# MCU.net
KiCad netlist of a schematic drawn in Altium Designer
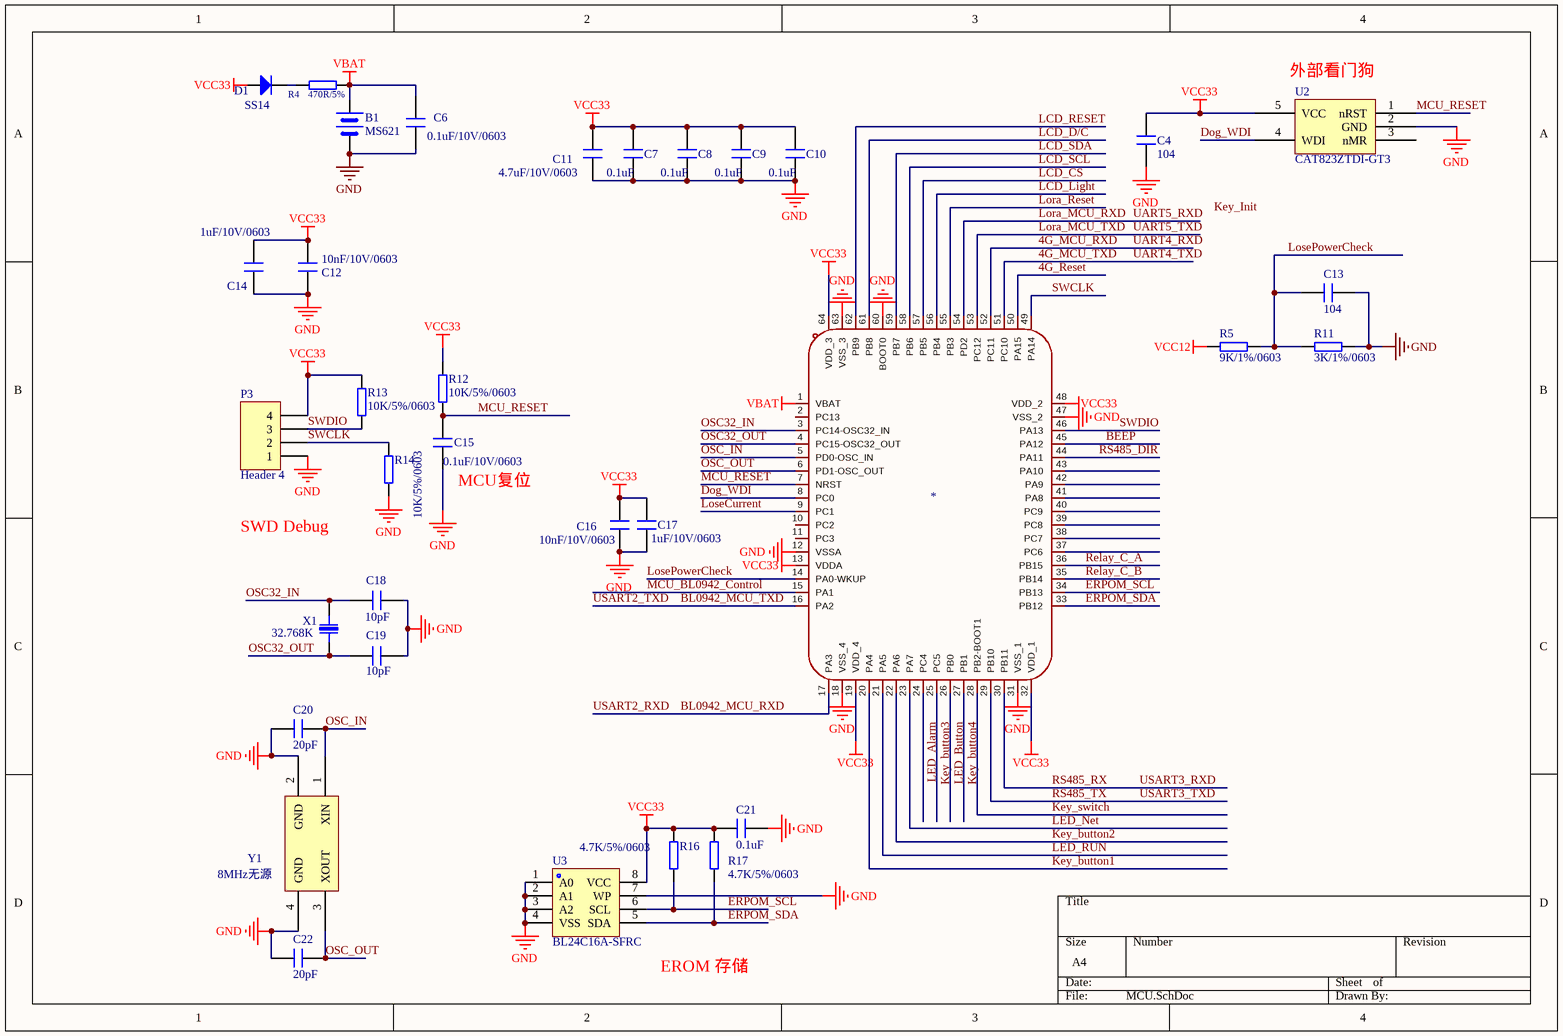
[diagram p0: MCU.SchDoc]

(export (version "E")
  (design (tool "Eeschema 10.0.6"))
  (components
    (comp (ref "B1") (value "MS621") (footprint "MS621") (libsource (lib "ES_Schematic") (part "BATTERY")))
    (comp (ref "C4") (value "104") (footprint "0603R") (libsource (lib "ES_Schematic") (part "CAP")))
    (comp (ref "C6")
      (value "0.1uF/10V/0603")
      (footprint "0603R")
      (libsource (lib "ES_Schematic") (part "CAP_1"))
    )
    (comp (ref "C7") (value "0.1uF") (footprint "0603R") (libsource (lib "ES_Schematic") (part "CAP_1")))
    (comp (ref "C8") (value "0.1uF") (footprint "0603R") (libsource (lib "ES_Schematic") (part "CAP_1")))
    (comp (ref "C9") (value "0.1uF") (footprint "0603R") (libsource (lib "ES_Schematic") (part "CAP_1")))
    (comp (ref "C10") (value "0.1uF") (footprint "0603R") (libsource (lib "ES_Schematic") (part "CAP_1")))
    (comp (ref "C11")
      (value "4.7uF/10V/0603")
      (footprint "0603R")
      (libsource (lib "ES_Schematic") (part "CAP_1"))
    )
    (comp (ref "C12")
      (value "10nF/10V/0603")
      (footprint "0603R")
      (libsource (lib "ES_Schematic") (part "CAP_1"))
    )
    (comp (ref "C13") (value "104") (footprint "0603R") (libsource (lib "ES_Schematic") (part "CAP")))
    (comp (ref "C14")
      (value "1uF/10V/0603")
      (footprint "0603R")
      (libsource (lib "ES_Schematic") (part "CAP_1"))
    )
    (comp (ref "C15")
      (value "0.1uF/10V/0603")
      (footprint "0603R")
      (libsource (lib "ES_Schematic") (part "CAP_1"))
    )
    (comp (ref "C16")
      (value "10nF/10V/0603")
      (footprint "0603R")
      (libsource (lib "ES_Schematic") (part "CAP_1"))
    )
    (comp (ref "C17")
      (value "1uF/10V/0603")
      (footprint "0603R")
      (libsource (lib "ES_Schematic") (part "CAP_1"))
    )
    (comp (ref "C18") (value "10pF") (footprint "0603r") (libsource (lib "ES_Schematic") (part "CAP")))
    (comp (ref "C19") (value "10pF") (footprint "0603r") (libsource (lib "ES_Schematic") (part "CAP")))
    (comp (ref "C20") (value "20pF") (footprint "0603r") (libsource (lib "ES_Schematic") (part "CAP")))
    (comp (ref "C21") (value "0.1uF") (footprint "0603R") (libsource (lib "ES_Schematic") (part "CAP_1")))
    (comp (ref "C22") (value "20pF") (footprint "0603r") (libsource (lib "ES_Schematic") (part "CAP")))
    (comp (ref "D1") (value "SS14") (footprint "SOD323") (libsource (lib "ES_Schematic") (part "DIODE")))
    (comp (ref "P3")
      (value "Header 4")
      (footprint "HDR1X4")
      (description "Header, 4-Pin")
      (fields (field (name "PUBLISHER") "Altium Limited"))
      (libsource (lib "Miscellaneous Connectors") (part "Header 4"))
    )
    (comp (ref "R4") (value "470R/5%") (footprint "0603R") (libsource (lib "ES_Schematic") (part "RES")))
    (comp (ref "R5") (value "9K/1%/0603") (footprint "0603R") (libsource (lib "ES_Schematic") (part "RES")))
    (comp (ref "R11") (value "3K/1%/0603") (footprint "0603R") (libsource (lib "ES_Schematic") (part "RES")))
    (comp (ref "R12") (value "10K/5%/0603") (footprint "0603r") (libsource (lib "ES_Schematic") (part "RES")))
    (comp (ref "R13") (value "10K/5%/0603") (footprint "0603r") (libsource (lib "ES_Schematic") (part "RES")))
    (comp (ref "R14") (value "10K/5%/0603") (footprint "0603r") (libsource (lib "ES_Schematic") (part "RES")))
    (comp (ref "R16")
      (value "4.7K/5%/0603")
      (footprint "0603R")
      (libsource (lib "ES_Schematic") (part "RES"))
    )
    (comp (ref "R17")
      (value "4.7K/5%/0603")
      (footprint "0603R")
      (libsource (lib "ES_Schematic") (part "RES"))
    )
    (comp (ref "U1")
      (value "*")
      (footprint "LQFP64")
      (libsource (lib "altium-import") (part "root_0_N32G452REL7_"))
    )
    (comp (ref "U2")
      (value "CAT823ZTDI-GT3")
      (footprint "SOT-23-5")
      (libsource (lib "ES_Schematic") (part "CAT823"))
    )
    (comp (ref "U3")
      (value "BL24C16A-SFRC")
      (footprint "TSSOP8")
      (libsource (lib "ES_Schematic") (part "24LC02"))
    )
    (comp (ref "X1") (value "32.768K") (footprint "Y3215") (libsource (lib "ES_Schematic") (part "XTAL")))
    (comp (ref "Y1") (value "8MHz无源") (footprint "3225") (libsource (lib "others") (part "12MHz无源")))
  )
  (nets
    (net (code "1") (name "/4G_MCU_RXD") (class "Default")
      (node (ref "U1") (pin "52") (pinfunction "PC11_52") (pintype "passive"))
    )
    (net (code "2") (name "/4G_MCU_TXD") (class "Default")
      (node (ref "U1") (pin "51") (pinfunction "PC10_51") (pintype "passive"))
    )
    (net (code "3") (name "/4G_Reset") (class "Default")
      (node (ref "U1") (pin "50") (pinfunction "PA15_50") (pintype "passive"))
    )
    (net (code "4") (name "/BEEP") (class "Default")
      (node (ref "U1") (pin "45") (pinfunction "PA12_45") (pintype "passive"))
    )
    (net (code "5") (name "/BL0942_MCU_RXD") (class "Default")
      (node (ref "U1") (pin "17") (pinfunction "PA3_17") (pintype "passive"))
    )
    (net (code "6") (name "/BL0942_MCU_TXD") (class "Default")
      (node (ref "U1") (pin "16") (pinfunction "PA2_16") (pintype "passive"))
    )
    (net (code "7") (name "/Dog_WDI") (class "Default")
      (node (ref "U1") (pin "8") (pinfunction "PC0_8") (pintype "passive"))
      (node (ref "U2") (pin "4") (pinfunction "WDI_4") (pintype "passive"))
    )
    (net (code "8") (name "/ERPOM_SCL") (class "Default")
      (node (ref "R16") (pin "2") (pinfunction "2_2") (pintype "passive"))
      (node (ref "U1") (pin "34") (pinfunction "PB13_34") (pintype "passive"))
      (node (ref "U3") (pin "6") (pinfunction "SCL_6") (pintype "passive"))
    )
    (net (code "9") (name "/ERPOM_SDA") (class "Default")
      (node (ref "R17") (pin "2") (pinfunction "2_2") (pintype "passive"))
      (node (ref "U1") (pin "33") (pinfunction "PB12_33") (pintype "passive"))
      (node (ref "U3") (pin "5") (pinfunction "SDA_5") (pintype "passive"))
    )
    (net (code "11") (name "/Key_button1") (class "Default")
      (node (ref "U1") (pin "20") (pinfunction "PA4_20") (pintype "passive"))
    )
    (net (code "12") (name "/Key_button2") (class "Default")
      (node (ref "U1") (pin "22") (pinfunction "PA6_22") (pintype "passive"))
    )
    (net (code "13") (name "/Key_button3") (class "Default")
      (node (ref "U1") (pin "25") (pinfunction "PC5_25") (pintype "passive"))
    )
    (net (code "14") (name "/Key_button4") (class "Default")
      (node (ref "U1") (pin "27") (pinfunction "PB1_27") (pintype "passive"))
    )
    (net (code "15") (name "/Key_switch") (class "Default")
      (node (ref "U1") (pin "28") (pinfunction "PB2-BOOT1_28") (pintype "passive"))
    )
    (net (code "16") (name "/LCD_CS") (class "Default")
      (node (ref "U1") (pin "57") (pinfunction "PB5_57") (pintype "passive"))
    )
    (net (code "17") (name "/LCD_D{slash}C") (class "Default")
      (node (ref "U1") (pin "61") (pinfunction "PB8_61") (pintype "passive"))
    )
    (net (code "18") (name "/LCD_Light") (class "Default")
      (node (ref "U1") (pin "56") (pinfunction "PB4_56") (pintype "passive"))
    )
    (net (code "19") (name "/LCD_RESET") (class "Default")
      (node (ref "U1") (pin "62") (pinfunction "PB9_62") (pintype "passive"))
    )
    (net (code "20") (name "/LCD_SCL") (class "Default")
      (node (ref "U1") (pin "58") (pinfunction "PB6_58") (pintype "passive"))
    )
    (net (code "21") (name "/LCD_SDA") (class "Default")
      (node (ref "U1") (pin "59") (pinfunction "PB7_59") (pintype "passive"))
    )
    (net (code "22") (name "/LED_Alarm") (class "Default")
      (node (ref "U1") (pin "24") (pinfunction "PC4_24") (pintype "passive"))
    )
    (net (code "23") (name "/LED_Button") (class "Default")
      (node (ref "U1") (pin "26") (pinfunction "PB0_26") (pintype "passive"))
    )
    (net (code "24") (name "/LED_Net") (class "Default")
      (node (ref "U1") (pin "23") (pinfunction "PA7_23") (pintype "passive"))
    )
    (net (code "25") (name "/LED_RUN") (class "Default")
      (node (ref "U1") (pin "21") (pinfunction "PA5_21") (pintype "passive"))
    )
    (net (code "26") (name "/Lora_MCU_RXD") (class "Default")
      (node (ref "U1") (pin "54") (pinfunction "PD2_54") (pintype "passive"))
    )
    (net (code "27") (name "/Lora_MCU_TXD") (class "Default")
      (node (ref "U1") (pin "53") (pinfunction "PC12_53") (pintype "passive"))
    )
    (net (code "28") (name "/Lora_Reset") (class "Default")
      (node (ref "U1") (pin "55") (pinfunction "PB3_55") (pintype "passive"))
    )
    (net (code "29") (name "/LoseCurrent") (class "Default")
      (node (ref "U1") (pin "9") (pinfunction "PC1_9") (pintype "passive"))
    )
    (net (code "30") (name "/LosePowerCheck") (class "Default")
      (node (ref "C13") (pin "2") (pinfunction "2_2") (pintype "passive"))
      (node (ref "R11") (pin "2") (pinfunction "2_2") (pintype "passive"))
      (node (ref "R5") (pin "2") (pinfunction "2_2") (pintype "passive"))
      (node (ref "U1") (pin "14") (pinfunction "PA0-WKUP_14") (pintype "passive"))
    )
    (net (code "31") (name "/MCU_BL0942_Control") (class "Default")
      (node (ref "U1") (pin "15") (pinfunction "PA1_15") (pintype "passive"))
    )
    (net (code "32") (name "/MCU_RESET") (class "Default")
      (node (ref "C15") (pin "2") (pinfunction "2_2") (pintype "passive"))
      (node (ref "R12") (pin "1") (pinfunction "1_1") (pintype "passive"))
      (node (ref "U1") (pin "7") (pinfunction "NRST_7") (pintype "passive"))
      (node (ref "U2") (pin "1") (pinfunction "nRST_1") (pintype "passive"))
    )
    (net (code "33") (name "/OSC32_IN") (class "Default")
      (node (ref "C18") (pin "1") (pinfunction "1_1") (pintype "passive"))
      (node (ref "U1") (pin "3") (pinfunction "PC14-OSC32_IN_3") (pintype "passive"))
      (node (ref "X1") (pin "2") (pinfunction "2_2") (pintype "passive"))
    )
    (net (code "34") (name "/OSC32_OUT") (class "Default")
      (node (ref "C19") (pin "2") (pinfunction "2_2") (pintype "passive"))
      (node (ref "U1") (pin "4") (pinfunction "PC15-OSC32_OUT_4") (pintype "passive"))
      (node (ref "X1") (pin "1") (pinfunction "1_1") (pintype "passive"))
    )
    (net (code "35") (name "/OSC_IN") (class "Default")
      (node (ref "C20") (pin "2") (pinfunction "2_2") (pintype "passive"))
      (node (ref "U1") (pin "5") (pinfunction "PD0-OSC_IN_5") (pintype "passive"))
      (node (ref "Y1") (pin "1") (pinfunction "XIN_1") (pintype "passive"))
    )
    (net (code "36") (name "/OSC_OUT") (class "Default")
      (node (ref "C22") (pin "2") (pinfunction "2_2") (pintype "passive"))
      (node (ref "U1") (pin "6") (pinfunction "PD1-OSC_OUT_6") (pintype "passive"))
      (node (ref "Y1") (pin "3") (pinfunction "XOUT_3") (pintype "passive"))
    )
    (net (code "37") (name "/RS485_DIR") (class "Default")
      (node (ref "U1") (pin "44") (pinfunction "PA11_44") (pintype "passive"))
    )
    (net (code "38") (name "/RS485_RX") (class "Default")
      (node (ref "U1") (pin "30") (pinfunction "PB11_30") (pintype "passive"))
    )
    (net (code "39") (name "/RS485_TX") (class "Default")
      (node (ref "U1") (pin "29") (pinfunction "PB10_29") (pintype "passive"))
    )
    (net (code "40") (name "/Relay_C_A") (class "Default")
      (node (ref "U1") (pin "36") (pinfunction "PB15_36") (pintype "passive"))
    )
    (net (code "41") (name "/Relay_C_B") (class "Default")
      (node (ref "U1") (pin "35") (pinfunction "PB14_35") (pintype "passive"))
    )
    (net (code "42") (name "/SWCLK") (class "Default")
      (node (ref "P3") (pin "2") (pinfunction "2_2") (pintype "passive"))
      (node (ref "R14") (pin "2") (pinfunction "2_2") (pintype "passive"))
      (node (ref "U1") (pin "49") (pinfunction "PA14_49") (pintype "passive"))
    )
    (net (code "43") (name "/SWDIO") (class "Default")
      (node (ref "P3") (pin "3") (pinfunction "3_3") (pintype "passive"))
      (node (ref "R13") (pin "1") (pinfunction "1_1") (pintype "passive"))
      (node (ref "U1") (pin "46") (pinfunction "PA13_46") (pintype "passive"))
    )
    (net (code "44") (name "GND") (class "Default")
      (node (ref "B1") (pin "2") (pinfunction "2_2") (pintype "passive"))
      (node (ref "C10") (pin "1") (pinfunction "1_1") (pintype "passive"))
      (node (ref "C11") (pin "1") (pinfunction "1_1") (pintype "passive"))
      (node (ref "C12") (pin "1") (pinfunction "1_1") (pintype "passive"))
      (node (ref "C13") (pin "1") (pinfunction "1_1") (pintype "passive"))
      (node (ref "C14") (pin "1") (pinfunction "1_1") (pintype "passive"))
      (node (ref "C15") (pin "1") (pinfunction "1_1") (pintype "passive"))
      (node (ref "C16") (pin "1") (pinfunction "1_1") (pintype "passive"))
      (node (ref "C17") (pin "1") (pinfunction "1_1") (pintype "passive"))
      (node (ref "C18") (pin "2") (pinfunction "2_2") (pintype "passive"))
      (node (ref "C19") (pin "1") (pinfunction "1_1") (pintype "passive"))
      (node (ref "C20") (pin "1") (pinfunction "1_1") (pintype "passive"))
      (node (ref "C21") (pin "1") (pinfunction "1_1") (pintype "passive"))
      (node (ref "C22") (pin "1") (pinfunction "1_1") (pintype "passive"))
      (node (ref "C4") (pin "1") (pinfunction "1_1") (pintype "passive"))
      (node (ref "C6") (pin "1") (pinfunction "1_1") (pintype "passive"))
      (node (ref "C7") (pin "1") (pinfunction "1_1") (pintype "passive"))
      (node (ref "C8") (pin "1") (pinfunction "1_1") (pintype "passive"))
      (node (ref "C9") (pin "1") (pinfunction "1_1") (pintype "passive"))
      (node (ref "P3") (pin "1") (pinfunction "1_1") (pintype "passive"))
      (node (ref "R11") (pin "1") (pinfunction "1_1") (pintype "passive"))
      (node (ref "R14") (pin "1") (pinfunction "1_1") (pintype "passive"))
      (node (ref "U1") (pin "12") (pinfunction "VSSA_12") (pintype "passive"))
      (node (ref "U1") (pin "18") (pinfunction "VSS_4_18") (pintype "passive"))
      (node (ref "U1") (pin "31") (pinfunction "VSS_1_31") (pintype "passive"))
      (node (ref "U1") (pin "47") (pinfunction "VSS_2_47") (pintype "passive"))
      (node (ref "U1") (pin "60") (pinfunction "BOOT0_60") (pintype "passive"))
      (node (ref "U1") (pin "63") (pinfunction "VSS_3_63") (pintype "passive"))
      (node (ref "U2") (pin "2") (pinfunction "GND_2") (pintype "passive"))
      (node (ref "U3") (pin "1") (pinfunction "A0_1") (pintype "passive"))
      (node (ref "U3") (pin "2") (pinfunction "A1_2") (pintype "passive"))
      (node (ref "U3") (pin "3") (pinfunction "A2_3") (pintype "passive"))
      (node (ref "U3") (pin "4") (pinfunction "VSS_4") (pintype "passive"))
      (node (ref "U3") (pin "7") (pinfunction "WP_7") (pintype "passive"))
      (node (ref "Y1") (pin "2") (pinfunction "GND_2") (pintype "passive"))
      (node (ref "Y1") (pin "4") (pinfunction "GND_4") (pintype "passive"))
    )
    (net (code "45") (name "Net-(D1-K)") (class "Default")
      (node (ref "D1") (pin "1") (pinfunction "K_1") (pintype "passive"))
      (node (ref "R4") (pin "2") (pinfunction "2_2") (pintype "passive"))
    )
    (net (code "46") (name "VBAT") (class "Default")
      (node (ref "B1") (pin "1") (pinfunction "1_1") (pintype "passive"))
      (node (ref "C6") (pin "2") (pinfunction "2_2") (pintype "passive"))
      (node (ref "R4") (pin "1") (pinfunction "1_1") (pintype "passive"))
      (node (ref "U1") (pin "1") (pinfunction "VBAT_1") (pintype "passive"))
    )
    (net (code "47") (name "VCC12") (class "Default")
      (node (ref "R5") (pin "1") (pinfunction "1_1") (pintype "passive"))
    )
    (net (code "48") (name "VCC33") (class "Default")
      (node (ref "C10") (pin "2") (pinfunction "2_2") (pintype "passive"))
      (node (ref "C11") (pin "2") (pinfunction "2_2") (pintype "passive"))
      (node (ref "C12") (pin "2") (pinfunction "2_2") (pintype "passive"))
      (node (ref "C14") (pin "2") (pinfunction "2_2") (pintype "passive"))
      (node (ref "C16") (pin "2") (pinfunction "2_2") (pintype "passive"))
      (node (ref "C17") (pin "2") (pinfunction "2_2") (pintype "passive"))
      (node (ref "C21") (pin "2") (pinfunction "2_2") (pintype "passive"))
      (node (ref "C4") (pin "2") (pinfunction "2_2") (pintype "passive"))
      (node (ref "C7") (pin "2") (pinfunction "2_2") (pintype "passive"))
      (node (ref "C8") (pin "2") (pinfunction "2_2") (pintype "passive"))
      (node (ref "C9") (pin "2") (pinfunction "2_2") (pintype "passive"))
      (node (ref "D1") (pin "2") (pinfunction "A_2") (pintype "passive"))
      (node (ref "P3") (pin "4") (pinfunction "4_4") (pintype "passive"))
      (node (ref "R12") (pin "2") (pinfunction "2_2") (pintype "passive"))
      (node (ref "R13") (pin "2") (pinfunction "2_2") (pintype "passive"))
      (node (ref "R16") (pin "1") (pinfunction "1_1") (pintype "passive"))
      (node (ref "R17") (pin "1") (pinfunction "1_1") (pintype "passive"))
      (node (ref "U1") (pin "13") (pinfunction "VDDA_13") (pintype "passive"))
      (node (ref "U1") (pin "19") (pinfunction "VDD_4_19") (pintype "passive"))
      (node (ref "U1") (pin "32") (pinfunction "VDD_1_32") (pintype "passive"))
      (node (ref "U1") (pin "48") (pinfunction "VDD_2_48") (pintype "passive"))
      (node (ref "U1") (pin "64") (pinfunction "VDD_3_64") (pintype "passive"))
      (node (ref "U2") (pin "5") (pinfunction "VCC_5") (pintype "passive"))
      (node (ref "U3") (pin "8") (pinfunction "VCC_8") (pintype "passive"))
    )
    (net (code "49") (name "unconnected-(U1-PA8-Pad41)") (class "Default")
      (node (ref "U1") (pin "41") (pinfunction "PA8_41") (pintype "passive"))
    )
    (net (code "50") (name "unconnected-(U1-PA9-Pad42)") (class "Default")
      (node (ref "U1") (pin "42") (pinfunction "PA9_42") (pintype "passive"))
    )
    (net (code "51") (name "unconnected-(U1-PA10-Pad43)") (class "Default")
      (node (ref "U1") (pin "43") (pinfunction "PA10_43") (pintype "passive"))
    )
    (net (code "52") (name "unconnected-(U1-PC2-Pad10)") (class "Default")
      (node (ref "U1") (pin "10") (pinfunction "PC2_10") (pintype "passive"))
    )
    (net (code "53") (name "unconnected-(U1-PC3-Pad11)") (class "Default")
      (node (ref "U1") (pin "11") (pinfunction "PC3_11") (pintype "passive"))
    )
    (net (code "54") (name "unconnected-(U1-PC6-Pad37)") (class "Default")
      (node (ref "U1") (pin "37") (pinfunction "PC6_37") (pintype "passive"))
    )
    (net (code "55") (name "unconnected-(U1-PC7-Pad38)") (class "Default")
      (node (ref "U1") (pin "38") (pinfunction "PC7_38") (pintype "passive"))
    )
    (net (code "56") (name "unconnected-(U1-PC8-Pad39)") (class "Default")
      (node (ref "U1") (pin "39") (pinfunction "PC8_39") (pintype "passive"))
    )
    (net (code "57") (name "unconnected-(U1-PC9-Pad40)") (class "Default")
      (node (ref "U1") (pin "40") (pinfunction "PC9_40") (pintype "passive"))
    )
    (net (code "58") (name "unconnected-(U1-PC13-Pad2)") (class "Default")
      (node (ref "U1") (pin "2") (pinfunction "PC13_2") (pintype "passive"))
    )
    (net (code "59") (name "unconnected-(U2-nMR-Pad3)") (class "Default")
      (node (ref "U2") (pin "3") (pinfunction "nMR_3") (pintype "passive"))
    )
  )
)
